# design.net
KiCad netlist of a schematic drawn in Altium Designer
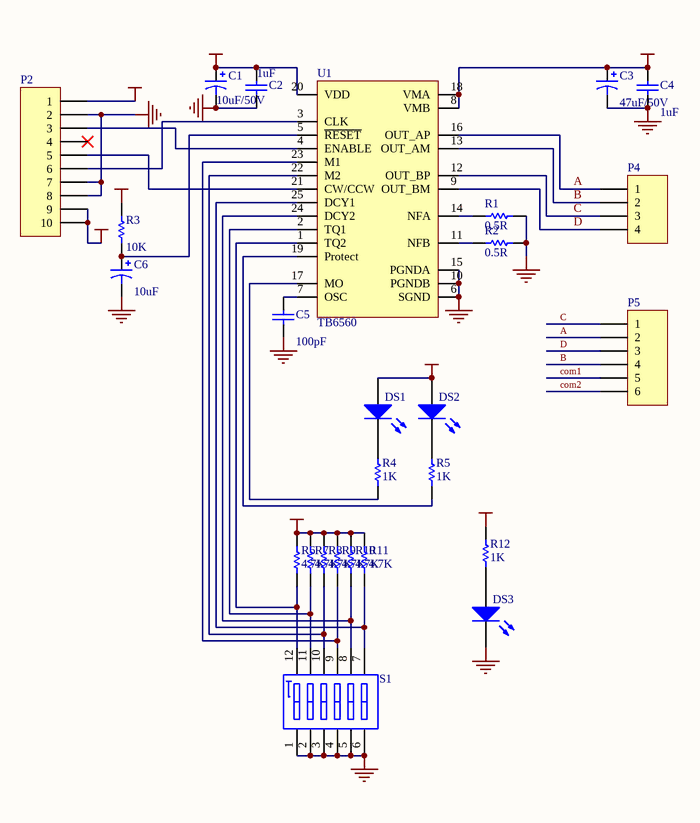
[diagram p0: 插式微步進驅動器.SCHDOC]

(export (version "E")
  (design (tool "Eeschema 10.0.6"))
  (components
    (comp (ref "C1")
      (value "10uF/50V")
      (footprint "CAPPR5-5x5")
      (description "Polarized Capacitor (Radial)")
      (fields (field (name "Comment") "Cap Pol1") (field (name "PUBLISHER") "Altium Limited"))
      (libsource (lib "Miscellaneous Devices") (part "Cap Pol1"))
    )
    (comp (ref "C2")
      (value "1uF")
      (footprint "CAPR5.08-7.8x3.2")
      (description "Capacitor")
      (fields (field (name "Comment") "Cap") (field (name "PUBLISHER") "Altium Limited"))
      (libsource (lib "Miscellaneous Devices") (part "Cap"))
    )
    (comp (ref "C3")
      (value "47uF/50V")
      (footprint "CAPPR5-5x5")
      (description "Polarized Capacitor (Radial)")
      (fields (field (name "Comment") "Cap Pol1") (field (name "PUBLISHER") "Altium Limited"))
      (libsource (lib "Miscellaneous Devices") (part "Cap Pol1"))
    )
    (comp (ref "C4")
      (value "1uF")
      (footprint "CAPR5.08-7.8x3.2")
      (description "Capacitor")
      (fields (field (name "Comment") "Cap") (field (name "PUBLISHER") "Altium Limited"))
      (libsource (lib "Miscellaneous Devices") (part "Cap"))
    )
    (comp (ref "C5")
      (value "100pF")
      (footprint "CAPR5.08-7.8x3.2")
      (description "Capacitor")
      (fields (field (name "Comment") "Cap") (field (name "PUBLISHER") "Altium Limited"))
      (libsource (lib "Miscellaneous Devices") (part "Cap"))
    )
    (comp (ref "C6")
      (value "10uF")
      (footprint "CAPPR5-5x5")
      (description "Polarized Capacitor (Radial)")
      (fields (field (name "Comment") "Cap Pol1") (field (name "PUBLISHER") "Altium Limited"))
      (libsource (lib "Miscellaneous Devices") (part "Cap Pol1"))
    )
    (comp (ref "DS1")
      (value "LED1")
      (footprint "LED 3mm T")
      (description "Typical RED GaAs LED")
      (fields (field (name "PUBLISHER") "Altium Limited"))
      (libsource (lib "Miscellaneous Devices") (part "LED1"))
    )
    (comp (ref "DS2")
      (value "LED1")
      (footprint "LED 3mm T")
      (description "Typical RED GaAs LED")
      (fields (field (name "PUBLISHER") "Altium Limited"))
      (libsource (lib "Miscellaneous Devices") (part "LED1"))
    )
    (comp (ref "DS3")
      (value "LED1")
      (footprint "LED 3mm T")
      (description "Typical RED GaAs LED")
      (fields (field (name "PUBLISHER") "Altium Limited"))
      (libsource (lib "Miscellaneous Devices") (part "LED1"))
    )
    (comp (ref "P2")
      (value "Header 10")
      (footprint "HDR1X10")
      (description "Header, 10-Pin")
      (fields (field (name "PUBLISHER") "Altium Limited"))
      (libsource (lib "Miscellaneous Connectors") (part "Header 10"))
    )
    (comp (ref "P4")
      (value "Header 4")
      (footprint "4pin夾式端子台")
      (description "Header, 4-Pin")
      (fields (field (name "PUBLISHER") "Altium Limited"))
      (libsource (lib "Miscellaneous Connectors") (part "Header 4"))
    )
    (comp (ref "P5")
      (value "Header 6")
      (footprint "HDR1X6")
      (description "Header, 6-Pin")
      (fields (field (name "PUBLISHER") "Altium Limited"))
      (libsource (lib "Miscellaneous Connectors") (part "Header 6"))
    )
    (comp (ref "R1")
      (value "0.5R")
      (footprint "¹qªý5.08mm")
      (description "Resistor")
      (fields (field (name "Comment") "Res1") (field (name "PUBLISHER") "Altium Limited"))
      (libsource (lib "Miscellaneous Devices") (part "Res1"))
    )
    (comp (ref "R2")
      (value "0.5R")
      (footprint "¹qªý5.08mm")
      (description "Resistor")
      (fields (field (name "Comment") "Res1") (field (name "PUBLISHER") "Altium Limited"))
      (libsource (lib "Miscellaneous Devices") (part "Res1"))
    )
    (comp (ref "R3")
      (value "10K")
      (footprint "AXIAL-0.3")
      (description "Resistor")
      (fields (field (name "Comment") "Res1") (field (name "PUBLISHER") "Altium Limited"))
      (libsource (lib "Miscellaneous Devices") (part "Res1"))
    )
    (comp (ref "R4")
      (value "1K")
      (footprint "AXIAL-0.3")
      (description "Resistor")
      (fields (field (name "Comment") "Res1") (field (name "PUBLISHER") "Altium Limited"))
      (libsource (lib "Miscellaneous Devices") (part "Res1"))
    )
    (comp (ref "R5")
      (value "1K")
      (footprint "AXIAL-0.3")
      (description "Resistor")
      (fields (field (name "Comment") "Res1") (field (name "PUBLISHER") "Altium Limited"))
      (libsource (lib "Miscellaneous Devices") (part "Res1"))
    )
    (comp (ref "R6")
      (value "4.7K")
      (footprint "AXIAL-0.3")
      (description "Resistor")
      (fields (field (name "Comment") "Res1") (field (name "PUBLISHER") "Altium Limited"))
      (libsource (lib "Miscellaneous Devices") (part "Res1"))
    )
    (comp (ref "R7")
      (value "4.7K")
      (footprint "AXIAL-0.3")
      (description "Resistor")
      (fields (field (name "Comment") "Res1") (field (name "PUBLISHER") "Altium Limited"))
      (libsource (lib "Miscellaneous Devices") (part "Res1"))
    )
    (comp (ref "R8")
      (value "4.7K")
      (footprint "AXIAL-0.3")
      (description "Resistor")
      (fields (field (name "Comment") "Res1") (field (name "PUBLISHER") "Altium Limited"))
      (libsource (lib "Miscellaneous Devices") (part "Res1"))
    )
    (comp (ref "R9")
      (value "4.7K")
      (footprint "AXIAL-0.3")
      (description "Resistor")
      (fields (field (name "Comment") "Res1") (field (name "PUBLISHER") "Altium Limited"))
      (libsource (lib "Miscellaneous Devices") (part "Res1"))
    )
    (comp (ref "R10")
      (value "4.7K")
      (footprint "AXIAL-0.3")
      (description "Resistor")
      (fields (field (name "Comment") "Res1") (field (name "PUBLISHER") "Altium Limited"))
      (libsource (lib "Miscellaneous Devices") (part "Res1"))
    )
    (comp (ref "R11")
      (value "4.7K")
      (footprint "AXIAL-0.3")
      (description "Resistor")
      (fields (field (name "Comment") "Res1") (field (name "PUBLISHER") "Altium Limited"))
      (libsource (lib "Miscellaneous Devices") (part "Res1"))
    )
    (comp (ref "R12")
      (value "1K")
      (footprint "AXIAL-0.3")
      (description "Resistor")
      (fields (field (name "Comment") "Res1") (field (name "PUBLISHER") "Altium Limited"))
      (libsource (lib "Miscellaneous Devices") (part "Res1"))
    )
    (comp (ref "S1")
      (value "SW DIP-6")
      (footprint "DIP-12/SW")
      (description "DIP Switch")
      (fields (field (name "PUBLISHER") "Altium Limited"))
      (libsource (lib "Miscellaneous Devices") (part "SW DIP-6"))
    )
    (comp (ref "U1") (value "TB6560") (footprint "TB6560AHQ") (libsource (lib "mydata") (part "TB6560")))
  )
  (nets
    (net (code "1") (name "+12") (class "Default")
      (node (ref "C3") (pin "1") (pinfunction "1_1") (pintype "passive"))
      (node (ref "C4") (pin "2") (pinfunction "2_2") (pintype "passive"))
      (node (ref "P2") (pin "10") (pinfunction "10_10") (pintype "passive"))
      (node (ref "P2") (pin "9") (pinfunction "9_9") (pintype "passive"))
      (node (ref "U1") (pin "18") (pinfunction "VMA_18") (pintype "passive"))
      (node (ref "U1") (pin "8") (pinfunction "VMB_8") (pintype "passive"))
    )
    (net (code "2") (name "/A") (class "Default")
      (node (ref "P4") (pin "1") (pinfunction "1_1") (pintype "passive"))
      (node (ref "P5") (pin "2") (pinfunction "2_2") (pintype "passive"))
      (node (ref "U1") (pin "16") (pinfunction "OUT_AP_16") (pintype "passive"))
    )
    (net (code "3") (name "/B") (class "Default")
      (node (ref "P4") (pin "2") (pinfunction "2_2") (pintype "passive"))
      (node (ref "P5") (pin "4") (pinfunction "4_4") (pintype "passive"))
      (node (ref "U1") (pin "13") (pinfunction "OUT_AM_13") (pintype "passive"))
    )
    (net (code "4") (name "/C") (class "Default")
      (node (ref "P4") (pin "3") (pinfunction "3_3") (pintype "passive"))
      (node (ref "P5") (pin "1") (pinfunction "1_1") (pintype "passive"))
      (node (ref "U1") (pin "12") (pinfunction "OUT_BP_12") (pintype "passive"))
    )
    (net (code "5") (name "/D") (class "Default")
      (node (ref "P4") (pin "4") (pinfunction "4_4") (pintype "passive"))
      (node (ref "P5") (pin "3") (pinfunction "3_3") (pintype "passive"))
      (node (ref "U1") (pin "9") (pinfunction "OUT_BM_9") (pintype "passive"))
    )
    (net (code "6") (name "/com1") (class "Default")
      (node (ref "P5") (pin "5") (pinfunction "5_5") (pintype "passive"))
    )
    (net (code "7") (name "/com2") (class "Default")
      (node (ref "P5") (pin "6") (pinfunction "6_6") (pintype "passive"))
    )
    (net (code "8") (name "GND") (class "Default")
      (node (ref "C1") (pin "2") (pinfunction "2_2") (pintype "passive"))
      (node (ref "C2") (pin "1") (pinfunction "1_1") (pintype "passive"))
      (node (ref "C3") (pin "2") (pinfunction "2_2") (pintype "passive"))
      (node (ref "C4") (pin "1") (pinfunction "1_1") (pintype "passive"))
      (node (ref "C5") (pin "1") (pinfunction "1_1") (pintype "passive"))
      (node (ref "C6") (pin "2") (pinfunction "2_2") (pintype "passive"))
      (node (ref "DS3") (pin "2") (pinfunction "K_2") (pintype "passive"))
      (node (ref "P2") (pin "2") (pinfunction "2_2") (pintype "passive"))
      (node (ref "P2") (pin "7") (pinfunction "7_7") (pintype "passive"))
      (node (ref "P2") (pin "8") (pinfunction "8_8") (pintype "passive"))
      (node (ref "R1") (pin "2") (pinfunction "2_2") (pintype "passive"))
      (node (ref "R2") (pin "2") (pinfunction "2_2") (pintype "passive"))
      (node (ref "S1") (pin "1") (pinfunction "A1_1") (pintype "passive"))
      (node (ref "S1") (pin "2") (pinfunction "A2_2") (pintype "passive"))
      (node (ref "S1") (pin "3") (pinfunction "A3_3") (pintype "passive"))
      (node (ref "S1") (pin "4") (pinfunction "A4_4") (pintype "passive"))
      (node (ref "S1") (pin "5") (pinfunction "A5_5") (pintype "passive"))
      (node (ref "S1") (pin "6") (pinfunction "A6_6") (pintype "passive"))
      (node (ref "U1") (pin "10") (pinfunction "PGNDB_10") (pintype "passive"))
      (node (ref "U1") (pin "15") (pinfunction "PGNDA_15") (pintype "passive"))
      (node (ref "U1") (pin "6") (pinfunction "SGND_6") (pintype "passive"))
    )
    (net (code "9") (name "Net-(DS1-K)") (class "Default")
      (node (ref "DS1") (pin "2") (pinfunction "K_2") (pintype "passive"))
      (node (ref "R4") (pin "2") (pinfunction "2_2") (pintype "passive"))
    )
    (net (code "10") (name "Net-(DS2-K)") (class "Default")
      (node (ref "DS2") (pin "2") (pinfunction "K_2") (pintype "passive"))
      (node (ref "R5") (pin "2") (pinfunction "2_2") (pintype "passive"))
    )
    (net (code "11") (name "Net-(DS3-A)") (class "Default")
      (node (ref "DS3") (pin "1") (pinfunction "A_1") (pintype "passive"))
      (node (ref "R12") (pin "1") (pinfunction "1_1") (pintype "passive"))
    )
    (net (code "12") (name "Net-(S1-B1)") (class "Default")
      (node (ref "R6") (pin "1") (pinfunction "1_1") (pintype "passive"))
      (node (ref "S1") (pin "12") (pinfunction "B1_12") (pintype "passive"))
      (node (ref "U1") (pin "1") (pinfunction "TQ2_1") (pintype "passive"))
    )
    (net (code "13") (name "Net-(S1-B2)") (class "Default")
      (node (ref "R7") (pin "1") (pinfunction "1_1") (pintype "passive"))
      (node (ref "S1") (pin "11") (pinfunction "B2_11") (pintype "passive"))
      (node (ref "U1") (pin "2") (pinfunction "TQ1_2") (pintype "passive"))
    )
    (net (code "14") (name "Net-(S1-B3)") (class "Default")
      (node (ref "R8") (pin "1") (pinfunction "1_1") (pintype "passive"))
      (node (ref "S1") (pin "10") (pinfunction "B3_10") (pintype "passive"))
      (node (ref "U1") (pin "22") (pinfunction "M2_22") (pintype "passive"))
    )
    (net (code "15") (name "Net-(S1-B4)") (class "Default")
      (node (ref "R9") (pin "1") (pinfunction "1_1") (pintype "passive"))
      (node (ref "S1") (pin "9") (pinfunction "B4_9") (pintype "passive"))
      (node (ref "U1") (pin "23") (pinfunction "M1_23") (pintype "passive"))
    )
    (net (code "16") (name "Net-(S1-B5)") (class "Default")
      (node (ref "R10") (pin "1") (pinfunction "1_1") (pintype "passive"))
      (node (ref "S1") (pin "8") (pinfunction "B5_8") (pintype "passive"))
      (node (ref "U1") (pin "24") (pinfunction "DCY2_24") (pintype "passive"))
    )
    (net (code "17") (name "Net-(S1-B6)") (class "Default")
      (node (ref "R11") (pin "1") (pinfunction "1_1") (pintype "passive"))
      (node (ref "S1") (pin "7") (pinfunction "B6_7") (pintype "passive"))
      (node (ref "U1") (pin "25") (pinfunction "DCY1_25") (pintype "passive"))
    )
    (net (code "18") (name "Net-(U1-CLK)") (class "Default")
      (node (ref "P2") (pin "6") (pinfunction "6_6") (pintype "passive"))
      (node (ref "U1") (pin "3") (pinfunction "CLK_3") (pintype "passive"))
    )
    (net (code "19") (name "Net-(U1-CW{slash}CCW)") (class "Default")
      (node (ref "P2") (pin "5") (pinfunction "5_5") (pintype "passive"))
      (node (ref "U1") (pin "21") (pinfunction "CW/CCW_21") (pintype "passive"))
    )
    (net (code "20") (name "Net-(U1-ENABLE)") (class "Default")
      (node (ref "P2") (pin "3") (pinfunction "3_3") (pintype "passive"))
      (node (ref "U1") (pin "4") (pinfunction "ENABLE_4") (pintype "passive"))
    )
    (net (code "21") (name "Net-(U1-MO)") (class "Default")
      (node (ref "R4") (pin "1") (pinfunction "1_1") (pintype "passive"))
      (node (ref "U1") (pin "17") (pinfunction "MO_17") (pintype "passive"))
    )
    (net (code "22") (name "Net-(U1-NFA)") (class "Default")
      (node (ref "R1") (pin "1") (pinfunction "1_1") (pintype "passive"))
      (node (ref "U1") (pin "14") (pinfunction "NFA_14") (pintype "passive"))
    )
    (net (code "23") (name "Net-(U1-NFB)") (class "Default")
      (node (ref "R2") (pin "1") (pinfunction "1_1") (pintype "passive"))
      (node (ref "U1") (pin "11") (pinfunction "NFB_11") (pintype "passive"))
    )
    (net (code "24") (name "Net-(U1-OSC)") (class "Default")
      (node (ref "C5") (pin "2") (pinfunction "2_2") (pintype "passive"))
      (node (ref "U1") (pin "7") (pinfunction "OSC_7") (pintype "passive"))
    )
    (net (code "25") (name "Net-(U1-Protect)") (class "Default")
      (node (ref "R5") (pin "1") (pinfunction "1_1") (pintype "passive"))
      (node (ref "U1") (pin "19") (pinfunction "Protect_19") (pintype "passive"))
    )
    (net (code "26") (name "Net-(U1-~{RESET})") (class "Default")
      (node (ref "C6") (pin "1") (pinfunction "1_1") (pintype "passive"))
      (node (ref "R3") (pin "1") (pinfunction "1_1") (pintype "passive"))
      (node (ref "U1") (pin "5") (pinfunction "~{RESET}_5") (pintype "passive"))
    )
    (net (code "27") (name "VCC") (class "Default")
      (node (ref "C1") (pin "1") (pinfunction "1_1") (pintype "passive"))
      (node (ref "C2") (pin "2") (pinfunction "2_2") (pintype "passive"))
      (node (ref "DS1") (pin "1") (pinfunction "A_1") (pintype "passive"))
      (node (ref "DS2") (pin "1") (pinfunction "A_1") (pintype "passive"))
      (node (ref "P2") (pin "1") (pinfunction "1_1") (pintype "passive"))
      (node (ref "R10") (pin "2") (pinfunction "2_2") (pintype "passive"))
      (node (ref "R11") (pin "2") (pinfunction "2_2") (pintype "passive"))
      (node (ref "R12") (pin "2") (pinfunction "2_2") (pintype "passive"))
      (node (ref "R3") (pin "2") (pinfunction "2_2") (pintype "passive"))
      (node (ref "R6") (pin "2") (pinfunction "2_2") (pintype "passive"))
      (node (ref "R7") (pin "2") (pinfunction "2_2") (pintype "passive"))
      (node (ref "R8") (pin "2") (pinfunction "2_2") (pintype "passive"))
      (node (ref "R9") (pin "2") (pinfunction "2_2") (pintype "passive"))
      (node (ref "U1") (pin "20") (pinfunction "VDD_20") (pintype "passive"))
    )
    (net (code "28") (name "unconnected-(P2-Pad4)") (class "Default")
      (node (ref "P2") (pin "4") (pinfunction "4_4") (pintype "passive+no_connect"))
    )
  )
)
